# SL6243A.net
KiCad netlist of a schematic drawn in Altium Designer
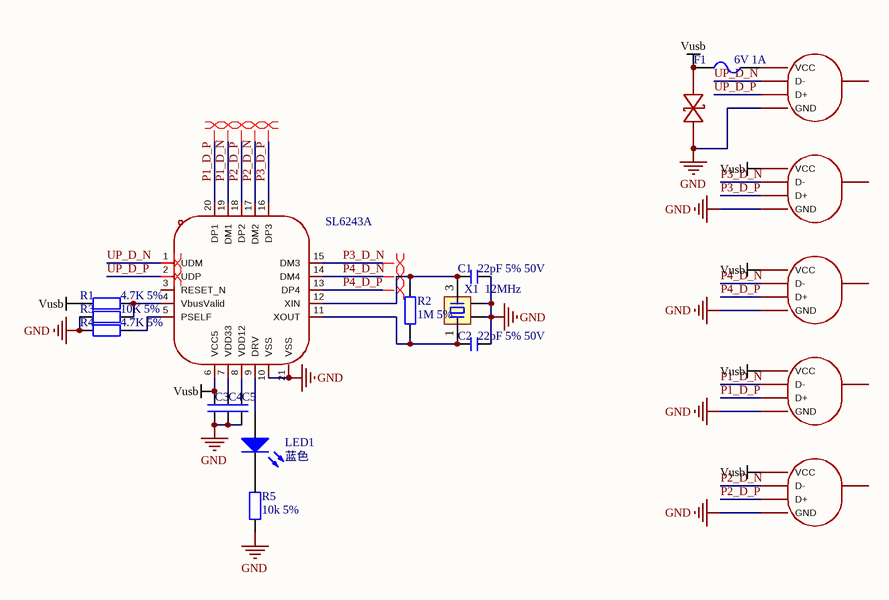
[diagram p0: SL6243A.SchDoc]

(export (version "E")
  (design (tool "Eeschema 10.0.6"))
  (components
    (comp (ref "C1")
      (value "22pF 5% 50V")
      (footprint "C0603_L")
      (description "贴片电容")
      (libsource (lib "0.1 - 电阻-电容-电感") (part "C"))
    )
    (comp (ref "C2")
      (value "22pF 5% 50V")
      (footprint "C0603_L")
      (description "贴片电容")
      (libsource (lib "0.1 - 电阻-电容-电感") (part "C"))
    )
    (comp (ref "C3")
      (value "4.7uF 10% 16V")
      (footprint "C0603_L")
      (description "贴片电容")
      (libsource (lib "0.1 - 电阻-电容-电感") (part "C"))
    )
    (comp (ref "C4")
      (value "4.7uF 10% 16V")
      (footprint "C0603_L")
      (description "贴片电容")
      (libsource (lib "0.1 - 电阻-电容-电感") (part "C"))
    )
    (comp (ref "C5")
      (value "4.7uF 10% 16V")
      (footprint "C0603_L")
      (description "贴片电容")
      (libsource (lib "0.1 - 电阻-电容-电感") (part "C"))
    )
    (comp (ref "D1")
      (value "smfj6.0ca_c151891")
      (footprint "SOD-123FL_L2.8-W1.8-LS3.7-BI")
      (fields (field (name "MANUFACTURER") "BORN(伯恩半导体)") (field (name "MANUFACTURERPART") "SMFJ6.0CA"))
      (libsource (lib "altium-import") (part "root_1_smfj6.0ca_c151891_"))
    )
    (comp (ref "F1")
      (value "6V 1A")
      (footprint "F0805")
      (description "0805自恢复保险座")
      (libsource (lib "0.1 - 电阻-电容-电感-保险丝-晶振-晶体-磁珠-电位器-法拉电容-馈通电容") (part "FUSE 1808"))
    )
    (comp (ref "LED1")
      (value "蓝色")
      (footprint "LED0603-FD")
      (description "贴片LED")
      (libsource (lib "0.3 - LED发光二极管-IR二极管_接收管-光耦") (part "LED"))
    )
    (comp (ref "R1")
      (value "4.7K 5%")
      (footprint "R0603_L")
      (description "贴片电阻")
      (libsource (lib "0.1 - 电阻-电容-电感") (part "R"))
    )
    (comp (ref "R2")
      (value "1M 5%")
      (footprint "R0603_L")
      (description "贴片电阻")
      (libsource (lib "0.1 - 电阻-电容-电感") (part "R"))
    )
    (comp (ref "R3")
      (value "10K 5%")
      (footprint "R0603_L")
      (description "贴片电阻")
      (libsource (lib "0.1 - 电阻-电容-电感") (part "R"))
    )
    (comp (ref "R4")
      (value "4.7K 5%")
      (footprint "R0603_L")
      (description "贴片电阻")
      (libsource (lib "0.1 - 电阻-电容-电感") (part "R"))
    )
    (comp (ref "R5")
      (value "10k 5%")
      (footprint "R0603_L")
      (description "贴片电阻")
      (libsource (lib "0.1 - 电阻-电容-电感") (part "R"))
    )
    (comp (ref "U1")
      (value "SL6243A")
      (footprint "QFN-20_L3.0-W3.0-P0.40-BL-EP1.7")
      (libsource (lib "Schlib1") (part "SL6243A"))
    )
    (comp (ref "USB1")
      (value "af 180°zjb13.7")
      (footprint "USB-A-TH_AF-ZJB13.7")
      (description "连接器类型:Type-A;标准:USB 2.0;公母:母;安装方式:直插;触点数量:4P;端口数量:1;额定电流 - 电源:1.5A;工作温度范围:-25℃~+85℃;")
      (fields (field (name "MANUFACTURER") "SHOU HAN(首韩)") (field (name "MANUFACTURERPART") "AF 180°ZJB13.7"))
      (libsource (lib "altium-import") (part "root_0_mirrored_af 180°zjb13.7_"))
    )
    (comp (ref "USB2")
      (value "af 180°zjb13.7")
      (footprint "USB-A-TH_AF-ZJB13.7")
      (description "连接器类型:Type-A;标准:USB 2.0;公母:母;安装方式:直插;触点数量:4P;端口数量:1;额定电流 - 电源:1.5A;工作温度范围:-25℃~+85℃;")
      (fields (field (name "MANUFACTURER") "SHOU HAN(首韩)") (field (name "MANUFACTURERPART") "AF 180°ZJB13.7"))
      (libsource (lib "altium-import") (part "root_0_mirrored_af 180°zjb13.7_"))
    )
    (comp (ref "USB3")
      (value "af 180°zjb13.7")
      (footprint "USB-A-TH_AF-ZJB13.7")
      (description "连接器类型:Type-A;标准:USB 2.0;公母:母;安装方式:直插;触点数量:4P;端口数量:1;额定电流 - 电源:1.5A;工作温度范围:-25℃~+85℃;")
      (fields (field (name "MANUFACTURER") "SHOU HAN(首韩)") (field (name "MANUFACTURERPART") "AF 180°ZJB13.7"))
      (libsource (lib "altium-import") (part "root_0_mirrored_af 180°zjb13.7_"))
    )
    (comp (ref "USB4")
      (value "af 180°zjb13.7")
      (footprint "USB-A-TH_AF-ZJB13.7")
      (description "连接器类型:Type-A;标准:USB 2.0;公母:母;安装方式:直插;触点数量:4P;端口数量:1;额定电流 - 电源:1.5A;工作温度范围:-25℃~+85℃;")
      (fields (field (name "MANUFACTURER") "SHOU HAN(首韩)") (field (name "MANUFACTURERPART") "AF 180°ZJB13.7"))
      (libsource (lib "altium-import") (part "root_0_mirrored_af 180°zjb13.7_"))
    )
    (comp (ref "USB5")
      (value "af 90° wjdg")
      (footprint "USB-A-TH_AF-WJDG")
      (description "连接器类型:Type-A;协议标准:USB 2.0;公母:母;安装方式:弯插;触点数量:4P;端口数量:1;额定电流 - 电源:1.5A;工作温度:-25℃~+85℃;")
      (fields (field (name "MANUFACTURER") "SHOU HAN(首韩)") (field (name "MANUFACTURERPART") "AF 90° WJDG"))
      (libsource (lib "altium-import") (part "root_0_mirrored_af 90° wjdg_"))
    )
    (comp (ref "X1")
      (value "12MHz")
      (footprint "OSC-3225-4P")
      (description "4脚无源晶振")
      (fields (field (name "版权归属") "封装库来自淘宝卖家 ID：黄晶宝石"))
      (libsource (lib "0.5 - 保险丝-晶振-光耦") (part "XTAL-4P"))
    )
  )
  (nets
    (net (code "1") (name "/P1_D_N") (class "Default")
      (node (ref "U1") (pin "19") (pinfunction "DM1_19") (pintype "passive"))
      (node (ref "USB4") (pin "2") (pinfunction "D-_2") (pintype "passive"))
    )
    (net (code "2") (name "/P1_D_P") (class "Default")
      (node (ref "U1") (pin "20") (pinfunction "DP1_20") (pintype "passive"))
      (node (ref "USB4") (pin "3") (pinfunction "D+_3") (pintype "passive"))
    )
    (net (code "3") (name "/P2_D_N") (class "Default")
      (node (ref "U1") (pin "17") (pinfunction "DM2_17") (pintype "passive"))
      (node (ref "USB5") (pin "2") (pinfunction "D-_2") (pintype "passive"))
    )
    (net (code "4") (name "/P2_D_P") (class "Default")
      (node (ref "U1") (pin "18") (pinfunction "DP2_18") (pintype "passive"))
      (node (ref "USB5") (pin "3") (pinfunction "D+_3") (pintype "passive"))
    )
    (net (code "5") (name "/P3_D_N") (class "Default")
      (node (ref "U1") (pin "15") (pinfunction "DM3_15") (pintype "passive"))
      (node (ref "USB2") (pin "2") (pinfunction "D-_2") (pintype "passive"))
    )
    (net (code "6") (name "/P3_D_P") (class "Default")
      (node (ref "U1") (pin "16") (pinfunction "DP3_16") (pintype "passive"))
      (node (ref "USB2") (pin "3") (pinfunction "D+_3") (pintype "passive"))
    )
    (net (code "7") (name "/P4_D_N") (class "Default")
      (node (ref "U1") (pin "14") (pinfunction "DM4_14") (pintype "passive"))
      (node (ref "USB3") (pin "2") (pinfunction "D-_2") (pintype "passive"))
    )
    (net (code "8") (name "/P4_D_P") (class "Default")
      (node (ref "U1") (pin "13") (pinfunction "DP4_13") (pintype "passive"))
      (node (ref "USB3") (pin "3") (pinfunction "D+_3") (pintype "passive"))
    )
    (net (code "9") (name "/UP_D_N") (class "Default")
      (node (ref "U1") (pin "1") (pinfunction "UDM_1") (pintype "passive"))
      (node (ref "USB1") (pin "2") (pinfunction "D-_2") (pintype "passive"))
    )
    (net (code "10") (name "/UP_D_P") (class "Default")
      (node (ref "U1") (pin "2") (pinfunction "UDP_2") (pintype "passive"))
      (node (ref "USB1") (pin "3") (pinfunction "D+_3") (pintype "passive"))
    )
    (net (code "11") (name "GND") (class "Default")
      (node (ref "C1") (pin "1") (pinfunction "1_1") (pintype "passive"))
      (node (ref "C2") (pin "1") (pinfunction "1_1") (pintype "passive"))
      (node (ref "C3") (pin "2") (pinfunction "2_2") (pintype "passive"))
      (node (ref "C4") (pin "2") (pinfunction "2_2") (pintype "passive"))
      (node (ref "C5") (pin "2") (pinfunction "2_2") (pintype "passive"))
      (node (ref "D1") (pin "1") (pinfunction "1_1") (pintype "passive"))
      (node (ref "R3") (pin "2") (pinfunction "2_2") (pintype "passive"))
      (node (ref "R4") (pin "1") (pinfunction "1_1") (pintype "passive"))
      (node (ref "R5") (pin "1") (pinfunction "1_1") (pintype "passive"))
      (node (ref "U1") (pin "10") (pinfunction "VSS_10") (pintype "passive"))
      (node (ref "U1") (pin "21") (pinfunction "VSS_21") (pintype "passive"))
      (node (ref "USB1") (pin "4") (pinfunction "GND_4") (pintype "passive"))
      (node (ref "USB2") (pin "4") (pinfunction "GND_4") (pintype "passive"))
      (node (ref "USB3") (pin "4") (pinfunction "GND_4") (pintype "passive"))
      (node (ref "USB4") (pin "4") (pinfunction "GND_4") (pintype "passive"))
      (node (ref "USB5") (pin "4") (pinfunction "GND_4") (pintype "passive"))
      (node (ref "X1") (pin "2") (pinfunction "2_2") (pintype "passive"))
      (node (ref "X1") (pin "4") (pinfunction "4_4") (pintype "passive"))
    )
    (net (code "12") (name "Net-(LED1-A)") (class "Default")
      (node (ref "LED1") (pin "1") (pinfunction "A_1") (pintype "passive"))
      (node (ref "U1") (pin "9") (pinfunction "DRV_9") (pintype "passive"))
    )
    (net (code "13") (name "Net-(LED1-K)") (class "Default")
      (node (ref "LED1") (pin "2") (pinfunction "K_2") (pintype "passive"))
      (node (ref "R5") (pin "2") (pinfunction "2_2") (pintype "passive"))
    )
    (net (code "14") (name "Net-(U1-PSELF)") (class "Default")
      (node (ref "R4") (pin "2") (pinfunction "2_2") (pintype "passive"))
      (node (ref "U1") (pin "5") (pinfunction "PSELF_5") (pintype "passive"))
    )
    (net (code "15") (name "Net-(U1-VDD12)") (class "Default")
      (node (ref "C5") (pin "1") (pinfunction "1_1") (pintype "passive"))
      (node (ref "U1") (pin "8") (pinfunction "VDD12_8") (pintype "passive"))
    )
    (net (code "16") (name "Net-(U1-VDD33)") (class "Default")
      (node (ref "C4") (pin "1") (pinfunction "1_1") (pintype "passive"))
      (node (ref "U1") (pin "7") (pinfunction "VDD33_7") (pintype "passive"))
    )
    (net (code "17") (name "Net-(U1-VbusValid)") (class "Default")
      (node (ref "R1") (pin "2") (pinfunction "2_2") (pintype "passive"))
      (node (ref "R3") (pin "1") (pinfunction "1_1") (pintype "passive"))
      (node (ref "U1") (pin "4") (pinfunction "VbusValid_4") (pintype "passive"))
    )
    (net (code "18") (name "Net-(U1-XIN)") (class "Default")
      (node (ref "C1") (pin "2") (pinfunction "2_2") (pintype "passive"))
      (node (ref "R2") (pin "1") (pinfunction "1_1") (pintype "passive"))
      (node (ref "U1") (pin "12") (pinfunction "XIN_12") (pintype "passive"))
      (node (ref "X1") (pin "3") (pinfunction "3_3") (pintype "passive"))
    )
    (net (code "19") (name "Net-(U1-XOUT)") (class "Default")
      (node (ref "C2") (pin "2") (pinfunction "2_2") (pintype "passive"))
      (node (ref "R2") (pin "2") (pinfunction "2_2") (pintype "passive"))
      (node (ref "U1") (pin "11") (pinfunction "XOUT_11") (pintype "passive"))
      (node (ref "X1") (pin "1") (pinfunction "1_1") (pintype "passive"))
    )
    (net (code "20") (name "Net-(USB1-VCC)") (class "Default")
      (node (ref "F1") (pin "1") (pinfunction "1_1") (pintype "passive"))
      (node (ref "USB1") (pin "1") (pinfunction "VCC_1") (pintype "passive"))
    )
    (net (code "21") (name "Vusb") (class "Default")
      (node (ref "C3") (pin "1") (pinfunction "1_1") (pintype "passive"))
      (node (ref "D1") (pin "2") (pinfunction "2_2") (pintype "passive"))
      (node (ref "F1") (pin "2") (pinfunction "2_2") (pintype "passive"))
      (node (ref "R1") (pin "1") (pinfunction "1_1") (pintype "passive"))
      (node (ref "U1") (pin "6") (pinfunction "VCC5_6") (pintype "passive"))
      (node (ref "USB2") (pin "1") (pinfunction "VCC_1") (pintype "passive"))
      (node (ref "USB3") (pin "1") (pinfunction "VCC_1") (pintype "passive"))
      (node (ref "USB4") (pin "1") (pinfunction "VCC_1") (pintype "passive"))
      (node (ref "USB5") (pin "1") (pinfunction "VCC_1") (pintype "passive"))
    )
    (net (code "22") (name "unconnected-(U1-RESET_N-Pad3)") (class "Default")
      (node (ref "U1") (pin "3") (pinfunction "RESET_N_3") (pintype "passive"))
    )
    (net (code "23") (name "unconnected-(USB1-SHLD-Pad5)") (class "Default")
      (node (ref "USB1") (pin "5") (pinfunction "SHLD_5") (pintype "passive"))
    )
    (net (code "24") (name "unconnected-(USB2-SHLD-Pad5)") (class "Default")
      (node (ref "USB2") (pin "5") (pinfunction "SHLD_5") (pintype "passive"))
    )
    (net (code "25") (name "unconnected-(USB3-SHLD-Pad5)") (class "Default")
      (node (ref "USB3") (pin "5") (pinfunction "SHLD_5") (pintype "passive"))
    )
    (net (code "26") (name "unconnected-(USB4-SHLD-Pad5)") (class "Default")
      (node (ref "USB4") (pin "5") (pinfunction "SHLD_5") (pintype "passive"))
    )
    (net (code "27") (name "unconnected-(USB5-SHLD-Pad5)") (class "Default")
      (node (ref "USB5") (pin "5") (pinfunction "SHLD_5") (pintype "passive"))
    )
  )
)
